# Schematic_RetroAV.net
KiCad netlist of a schematic drawn in EasyEDA
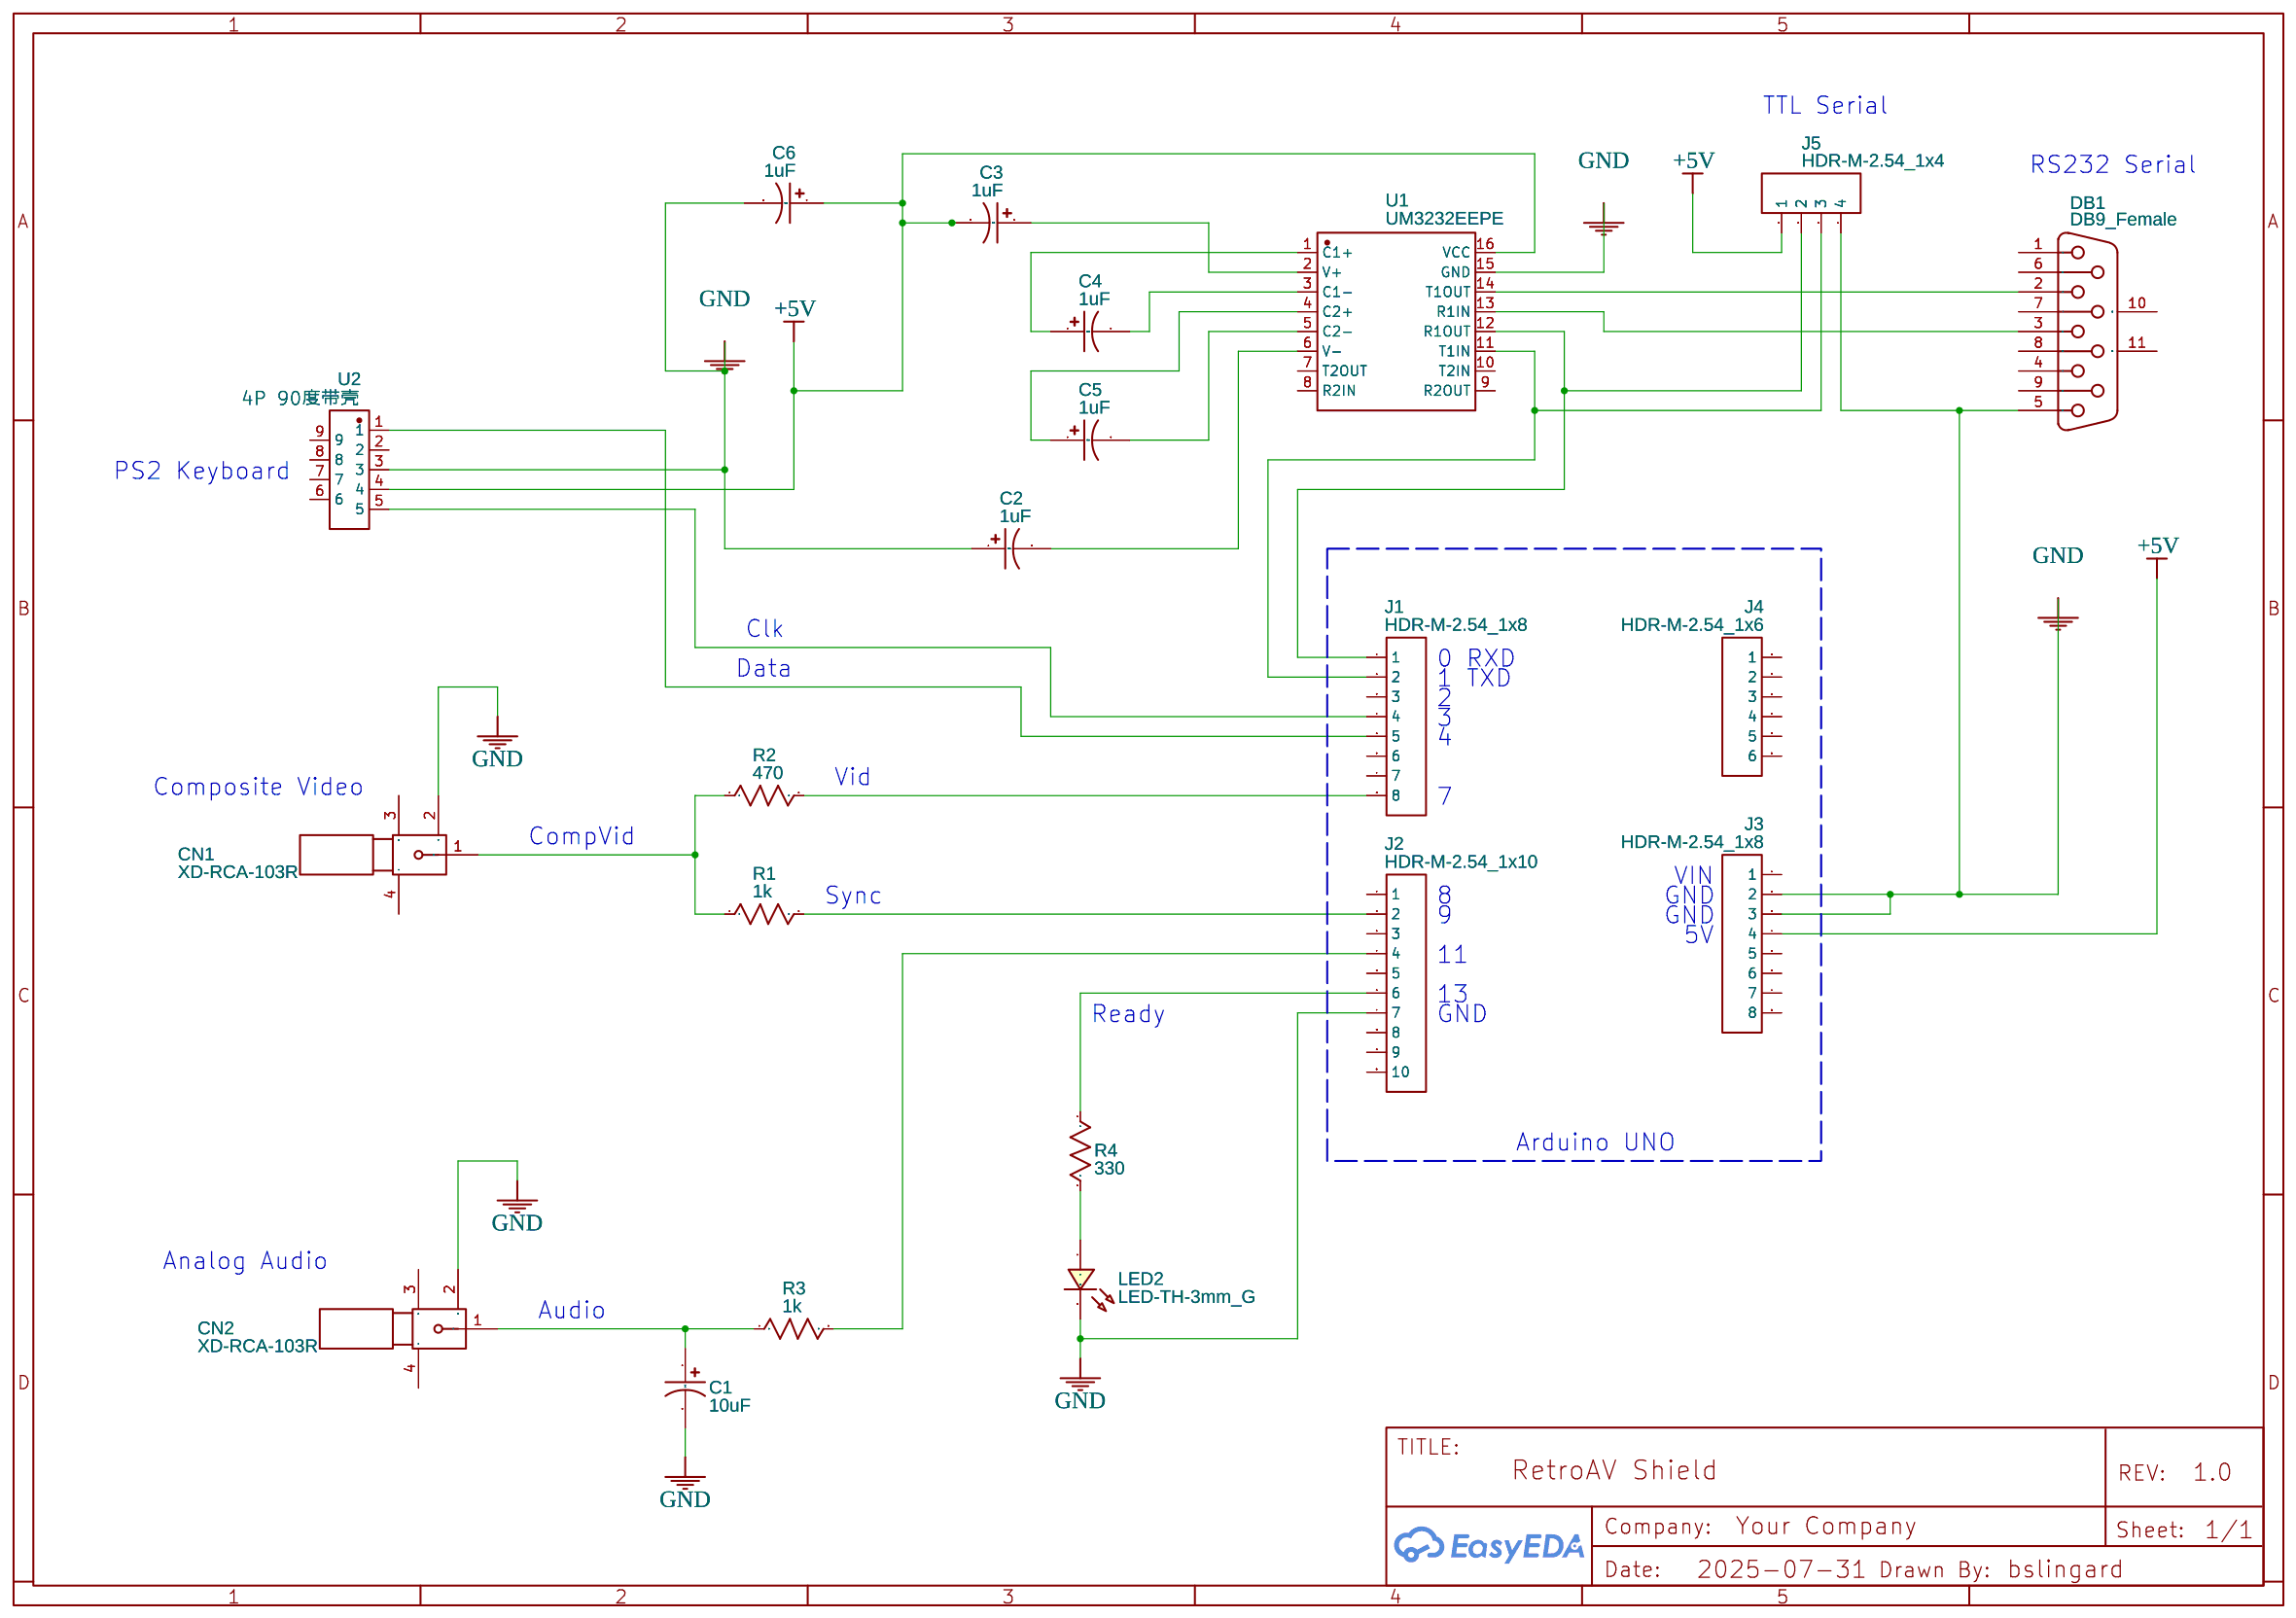
[diagram p0: schematic sheet]

(export (version "E")
  (design (tool "Eeschema 10.0.6"))
  (components
    (comp (ref "C1") (value "10uF") (libsource (lib "") (part "CE_TH_D3.0×F1.5_US_2")))
    (comp (ref "C2") (value "1uF") (libsource (lib "") (part "CE_TH_D3.0×F1.5_US")))
    (comp (ref "C3") (value "1uF") (libsource (lib "") (part "CE_TH_D3.0×F1.5_US_1")))
    (comp (ref "C4") (value "1uF") (libsource (lib "") (part "CE_TH_D3.0×F1.5_US")))
    (comp (ref "C5") (value "1uF") (libsource (lib "") (part "CE_TH_D3.0×F1.5_US")))
    (comp (ref "C6") (value "1uF") (libsource (lib "") (part "CE_TH_D3.0×F1.5_US_1")))
    (comp (ref "CN1")
      (value "XD-RCA-103R")
      (fields (field (name "Manufacturer") "LX(连欣科技)"))
      (libsource (lib "") (part "XD-RCA-103R"))
    )
    (comp (ref "CN2")
      (value "XD-RCA-103R")
      (fields (field (name "Manufacturer") "LX(连欣科技)"))
      (libsource (lib "") (part "XD-RCA-103R"))
    )
    (comp (ref "DB1")
      (value "DB9_Female")
      (fields (field (name "Manufacturer") "Ckmtw(灿科盟)"))
      (libsource (lib "") (part "DB9_Female"))
    )
    (comp (ref "J1") (value "HDR-M-2.54_1x8") (libsource (lib "") (part "HDR-M-2.54_1x8")))
    (comp (ref "J2") (value "HDR-M-2.54_1x10") (libsource (lib "") (part "HDR-M-2.54_1x10")))
    (comp (ref "J3") (value "HDR-M-2.54_1x8") (libsource (lib "") (part "HDR-M-2.54_1x8_1")))
    (comp (ref "J4") (value "HDR-M-2.54_1x6") (libsource (lib "") (part "HDR-M-2.54_1x6")))
    (comp (ref "J5") (value "HDR-M-2.54_1x4") (libsource (lib "") (part "HDR-M-2.54_1x4")))
    (comp (ref "LED2")
      (value "LED-TH-3mm_G")
      (fields
        (field (name "Manufacturer Part") "204-10SYGD/S530-E3")
        (field (name "Manufacturer") "EVERLIGHT(台湾亿光)")
      )
      (libsource (lib "") (part "LED-TH-3mm_G"))
    )
    (comp (ref "R1") (value "1k") (libsource (lib "") (part "R_0603_US_1")))
    (comp (ref "R2") (value "470") (libsource (lib "") (part "R_0603_US_1")))
    (comp (ref "R3") (value "1k") (libsource (lib "") (part "R_0603_US_1")))
    (comp (ref "R4") (value "330") (libsource (lib "") (part "R_0603_US")))
    (comp (ref "U1")
      (value "UM3232EEPE")
      (fields (field (name "Manufacturer") "Union(英联)"))
      (libsource (lib "") (part "UM3232EEPE"))
    )
    (comp (ref "U2") (value "4P 90度带壳") (libsource (lib "") (part "4P 90度带壳")))
  )
  (nets
    (net (code "1") (name "+5V") (class "Default")
      (node (ref "C3") (pin "2") (pinfunction "2_2") (pintype "unspecified"))
      (node (ref "C6") (pin "1") (pinfunction "1_1") (pintype "unspecified"))
      (node (ref "J3") (pin "4") (pinfunction "4_4") (pintype "unspecified"))
      (node (ref "J5") (pin "1") (pinfunction "1_1") (pintype "unspecified"))
      (node (ref "U1") (pin "16") (pinfunction "VCC_16") (pintype "unspecified"))
      (node (ref "U2") (pin "4") (pinfunction "4_4") (pintype "unspecified"))
    )
    (net (code "2") (name "GND") (class "Default")
      (node (ref "C1") (pin "2") (pinfunction "2_2") (pintype "unspecified"))
      (node (ref "C2") (pin "1") (pinfunction "1_1") (pintype "unspecified"))
      (node (ref "C6") (pin "2") (pinfunction "2_2") (pintype "unspecified"))
      (node (ref "CN1") (pin "2") (pinfunction "2_2") (pintype "unspecified"))
      (node (ref "CN2") (pin "2") (pinfunction "2_2") (pintype "unspecified"))
      (node (ref "DB1") (pin "5") (pinfunction "5_5") (pintype "input"))
      (node (ref "J2") (pin "7") (pinfunction "7_7") (pintype "unspecified"))
      (node (ref "J3") (pin "2") (pinfunction "2_2") (pintype "unspecified"))
      (node (ref "J3") (pin "3") (pinfunction "3_3") (pintype "unspecified"))
      (node (ref "J5") (pin "4") (pinfunction "4_4") (pintype "unspecified"))
      (node (ref "LED2") (pin "2") (pinfunction "2_2") (pintype "unspecified"))
      (node (ref "U1") (pin "15") (pinfunction "GND_15") (pintype "unspecified"))
      (node (ref "U2") (pin "3") (pinfunction "3_3") (pintype "unspecified"))
    )
    (net (code "3") (name "Net-(C1-Pad1)") (class "Default")
      (node (ref "C1") (pin "1") (pinfunction "1_1") (pintype "unspecified"))
      (node (ref "CN2") (pin "1") (pinfunction "1_1") (pintype "unspecified"))
      (node (ref "R3") (pin "1") (pinfunction "1_1") (pintype "unspecified"))
    )
    (net (code "4") (name "Net-(CN1-Pad1)") (class "Default")
      (node (ref "CN1") (pin "1") (pinfunction "1_1") (pintype "unspecified"))
      (node (ref "R1") (pin "1") (pinfunction "1_1") (pintype "unspecified"))
      (node (ref "R2") (pin "1") (pinfunction "1_1") (pintype "unspecified"))
    )
    (net (code "5") (name "Net-(J1-Pad4)") (class "Default")
      (node (ref "J1") (pin "4") (pinfunction "4_4") (pintype "unspecified"))
      (node (ref "U2") (pin "5") (pinfunction "5_5") (pintype "unspecified"))
    )
    (net (code "6") (name "Net-(J1-Pad5)") (class "Default")
      (node (ref "J1") (pin "5") (pinfunction "5_5") (pintype "unspecified"))
      (node (ref "U2") (pin "1") (pinfunction "1_1") (pintype "unspecified"))
    )
    (net (code "7") (name "Net-(J1-Pad8)") (class "Default")
      (node (ref "J1") (pin "8") (pinfunction "8_8") (pintype "unspecified"))
      (node (ref "R2") (pin "2") (pinfunction "2_2") (pintype "unspecified"))
    )
    (net (code "8") (name "Net-(J2-Pad2)") (class "Default")
      (node (ref "J2") (pin "2") (pinfunction "2_2") (pintype "unspecified"))
      (node (ref "R1") (pin "2") (pinfunction "2_2") (pintype "unspecified"))
    )
    (net (code "9") (name "Net-(J2-Pad4)") (class "Default")
      (node (ref "J2") (pin "4") (pinfunction "4_4") (pintype "unspecified"))
      (node (ref "R3") (pin "2") (pinfunction "2_2") (pintype "unspecified"))
    )
    (net (code "10") (name "Net-(J2-Pad6)") (class "Default")
      (node (ref "J2") (pin "6") (pinfunction "6_6") (pintype "unspecified"))
      (node (ref "R4") (pin "1") (pinfunction "1_1") (pintype "unspecified"))
    )
    (net (code "11") (name "Net-(LED2-Pad1)") (class "Default")
      (node (ref "LED2") (pin "1") (pinfunction "1_1") (pintype "unspecified"))
      (node (ref "R4") (pin "2") (pinfunction "2_2") (pintype "unspecified"))
    )
    (net (code "12") (name "Net-(U1-C1+)") (class "Default")
      (node (ref "C4") (pin "1") (pinfunction "1_1") (pintype "unspecified"))
      (node (ref "U1") (pin "1") (pinfunction "C1+_1") (pintype "unspecified"))
    )
    (net (code "13") (name "Net-(U1-C1-)") (class "Default")
      (node (ref "C4") (pin "2") (pinfunction "2_2") (pintype "unspecified"))
      (node (ref "U1") (pin "3") (pinfunction "C1-_3") (pintype "unspecified"))
    )
    (net (code "14") (name "Net-(U1-C2+)") (class "Default")
      (node (ref "C5") (pin "1") (pinfunction "1_1") (pintype "unspecified"))
      (node (ref "U1") (pin "4") (pinfunction "C2+_4") (pintype "unspecified"))
    )
    (net (code "15") (name "Net-(U1-C2-)") (class "Default")
      (node (ref "C5") (pin "2") (pinfunction "2_2") (pintype "unspecified"))
      (node (ref "U1") (pin "5") (pinfunction "C2-_5") (pintype "unspecified"))
    )
    (net (code "16") (name "Net-(U1-R1IN)") (class "Default")
      (node (ref "DB1") (pin "3") (pinfunction "3_3") (pintype "input"))
      (node (ref "U1") (pin "13") (pinfunction "R1IN_13") (pintype "unspecified"))
    )
    (net (code "17") (name "Net-(U1-R1OUT)") (class "Default")
      (node (ref "J1") (pin "1") (pinfunction "1_1") (pintype "unspecified"))
      (node (ref "J5") (pin "2") (pinfunction "2_2") (pintype "unspecified"))
      (node (ref "U1") (pin "12") (pinfunction "R1OUT_12") (pintype "unspecified"))
    )
    (net (code "18") (name "Net-(U1-T1IN)") (class "Default")
      (node (ref "J1") (pin "2") (pinfunction "2_2") (pintype "unspecified"))
      (node (ref "J5") (pin "3") (pinfunction "3_3") (pintype "unspecified"))
      (node (ref "U1") (pin "11") (pinfunction "T1IN_11") (pintype "unspecified"))
    )
    (net (code "19") (name "Net-(U1-T1OUT)") (class "Default")
      (node (ref "DB1") (pin "2") (pinfunction "2_2") (pintype "input"))
      (node (ref "U1") (pin "14") (pinfunction "T1OUT_14") (pintype "unspecified"))
    )
    (net (code "20") (name "Net-(U1-V+)") (class "Default")
      (node (ref "C3") (pin "1") (pinfunction "1_1") (pintype "unspecified"))
      (node (ref "U1") (pin "2") (pinfunction "V+_2") (pintype "unspecified"))
    )
    (net (code "21") (name "Net-(U1-V-)") (class "Default")
      (node (ref "C2") (pin "2") (pinfunction "2_2") (pintype "unspecified"))
      (node (ref "U1") (pin "6") (pinfunction "V-_6") (pintype "unspecified"))
    )
    (net (code "22") (name "unconnected-(CN1-Pad3)") (class "Default")
      (node (ref "CN1") (pin "3") (pinfunction "3_3") (pintype "unspecified"))
    )
    (net (code "23") (name "unconnected-(CN1-Pad4)") (class "Default")
      (node (ref "CN1") (pin "4") (pinfunction "4_4") (pintype "unspecified"))
    )
    (net (code "24") (name "unconnected-(CN2-Pad3)") (class "Default")
      (node (ref "CN2") (pin "3") (pinfunction "3_3") (pintype "unspecified"))
    )
    (net (code "25") (name "unconnected-(CN2-Pad4)") (class "Default")
      (node (ref "CN2") (pin "4") (pinfunction "4_4") (pintype "unspecified"))
    )
    (net (code "26") (name "unconnected-(DB1-MH1-Pad10)") (class "Default")
      (node (ref "DB1") (pin "10") (pinfunction "MH1_10") (pintype "input"))
    )
    (net (code "27") (name "unconnected-(DB1-MH2-Pad11)") (class "Default")
      (node (ref "DB1") (pin "11") (pinfunction "MH2_11") (pintype "input"))
    )
    (net (code "28") (name "unconnected-(DB1-Pad1)") (class "Default")
      (node (ref "DB1") (pin "1") (pinfunction "1_1") (pintype "input"))
    )
    (net (code "29") (name "unconnected-(DB1-Pad4)") (class "Default")
      (node (ref "DB1") (pin "4") (pinfunction "4_4") (pintype "input"))
    )
    (net (code "30") (name "unconnected-(DB1-Pad6)") (class "Default")
      (node (ref "DB1") (pin "6") (pinfunction "6_6") (pintype "input"))
    )
    (net (code "31") (name "unconnected-(DB1-Pad7)") (class "Default")
      (node (ref "DB1") (pin "7") (pinfunction "7_7") (pintype "input"))
    )
    (net (code "32") (name "unconnected-(DB1-Pad8)") (class "Default")
      (node (ref "DB1") (pin "8") (pinfunction "8_8") (pintype "input"))
    )
    (net (code "33") (name "unconnected-(DB1-Pad9)") (class "Default")
      (node (ref "DB1") (pin "9") (pinfunction "9_9") (pintype "input"))
    )
    (net (code "34") (name "unconnected-(J1-Pad3)") (class "Default")
      (node (ref "J1") (pin "3") (pinfunction "3_3") (pintype "unspecified"))
    )
    (net (code "35") (name "unconnected-(J1-Pad6)") (class "Default")
      (node (ref "J1") (pin "6") (pinfunction "6_6") (pintype "unspecified"))
    )
    (net (code "36") (name "unconnected-(J1-Pad7)") (class "Default")
      (node (ref "J1") (pin "7") (pinfunction "7_7") (pintype "unspecified"))
    )
    (net (code "37") (name "unconnected-(J2-Pad1)") (class "Default")
      (node (ref "J2") (pin "1") (pinfunction "1_1") (pintype "unspecified"))
    )
    (net (code "38") (name "unconnected-(J2-Pad3)") (class "Default")
      (node (ref "J2") (pin "3") (pinfunction "3_3") (pintype "unspecified"))
    )
    (net (code "39") (name "unconnected-(J2-Pad5)") (class "Default")
      (node (ref "J2") (pin "5") (pinfunction "5_5") (pintype "unspecified"))
    )
    (net (code "40") (name "unconnected-(J2-Pad8)") (class "Default")
      (node (ref "J2") (pin "8") (pinfunction "8_8") (pintype "unspecified"))
    )
    (net (code "41") (name "unconnected-(J2-Pad9)") (class "Default")
      (node (ref "J2") (pin "9") (pinfunction "9_9") (pintype "unspecified"))
    )
    (net (code "42") (name "unconnected-(J2-Pad10)") (class "Default")
      (node (ref "J2") (pin "10") (pinfunction "10_10") (pintype "unspecified"))
    )
    (net (code "43") (name "unconnected-(J3-Pad1)") (class "Default")
      (node (ref "J3") (pin "1") (pinfunction "1_1") (pintype "unspecified"))
    )
    (net (code "44") (name "unconnected-(J3-Pad5)") (class "Default")
      (node (ref "J3") (pin "5") (pinfunction "5_5") (pintype "unspecified"))
    )
    (net (code "45") (name "unconnected-(J3-Pad6)") (class "Default")
      (node (ref "J3") (pin "6") (pinfunction "6_6") (pintype "unspecified"))
    )
    (net (code "46") (name "unconnected-(J3-Pad7)") (class "Default")
      (node (ref "J3") (pin "7") (pinfunction "7_7") (pintype "unspecified"))
    )
    (net (code "47") (name "unconnected-(J3-Pad8)") (class "Default")
      (node (ref "J3") (pin "8") (pinfunction "8_8") (pintype "unspecified"))
    )
    (net (code "48") (name "unconnected-(J4-Pad1)") (class "Default")
      (node (ref "J4") (pin "1") (pinfunction "1_1") (pintype "input"))
    )
    (net (code "49") (name "unconnected-(J4-Pad2)") (class "Default")
      (node (ref "J4") (pin "2") (pinfunction "2_2") (pintype "input"))
    )
    (net (code "50") (name "unconnected-(J4-Pad3)") (class "Default")
      (node (ref "J4") (pin "3") (pinfunction "3_3") (pintype "input"))
    )
    (net (code "51") (name "unconnected-(J4-Pad4)") (class "Default")
      (node (ref "J4") (pin "4") (pinfunction "4_4") (pintype "input"))
    )
    (net (code "52") (name "unconnected-(J4-Pad5)") (class "Default")
      (node (ref "J4") (pin "5") (pinfunction "5_5") (pintype "input"))
    )
    (net (code "53") (name "unconnected-(J4-Pad6)") (class "Default")
      (node (ref "J4") (pin "6") (pinfunction "6_6") (pintype "input"))
    )
    (net (code "54") (name "unconnected-(U1-R2IN-Pad8)") (class "Default")
      (node (ref "U1") (pin "8") (pinfunction "R2IN_8") (pintype "unspecified"))
    )
    (net (code "55") (name "unconnected-(U1-R2OUT-Pad9)") (class "Default")
      (node (ref "U1") (pin "9") (pinfunction "R2OUT_9") (pintype "unspecified"))
    )
    (net (code "56") (name "unconnected-(U1-T2IN-Pad10)") (class "Default")
      (node (ref "U1") (pin "10") (pinfunction "T2IN_10") (pintype "unspecified"))
    )
    (net (code "57") (name "unconnected-(U1-T2OUT-Pad7)") (class "Default")
      (node (ref "U1") (pin "7") (pinfunction "T2OUT_7") (pintype "unspecified"))
    )
    (net (code "58") (name "unconnected-(U2-Pad2)") (class "Default")
      (node (ref "U2") (pin "2") (pinfunction "2_2") (pintype "unspecified"))
    )
    (net (code "59") (name "unconnected-(U2-Pad6)") (class "Default")
      (node (ref "U2") (pin "6") (pinfunction "6_6") (pintype "unspecified"))
    )
    (net (code "60") (name "unconnected-(U2-Pad7)") (class "Default")
      (node (ref "U2") (pin "7") (pinfunction "7_7") (pintype "unspecified"))
    )
    (net (code "61") (name "unconnected-(U2-Pad8)") (class "Default")
      (node (ref "U2") (pin "8") (pinfunction "8_8") (pintype "unspecified"))
    )
    (net (code "62") (name "unconnected-(U2-Pad9)") (class "Default")
      (node (ref "U2") (pin "9") (pinfunction "9_9") (pintype "unspecified"))
    )
  )
)
